# Cherry_MX.net
KiCad netlist of a schematic drawn in Altium Designer
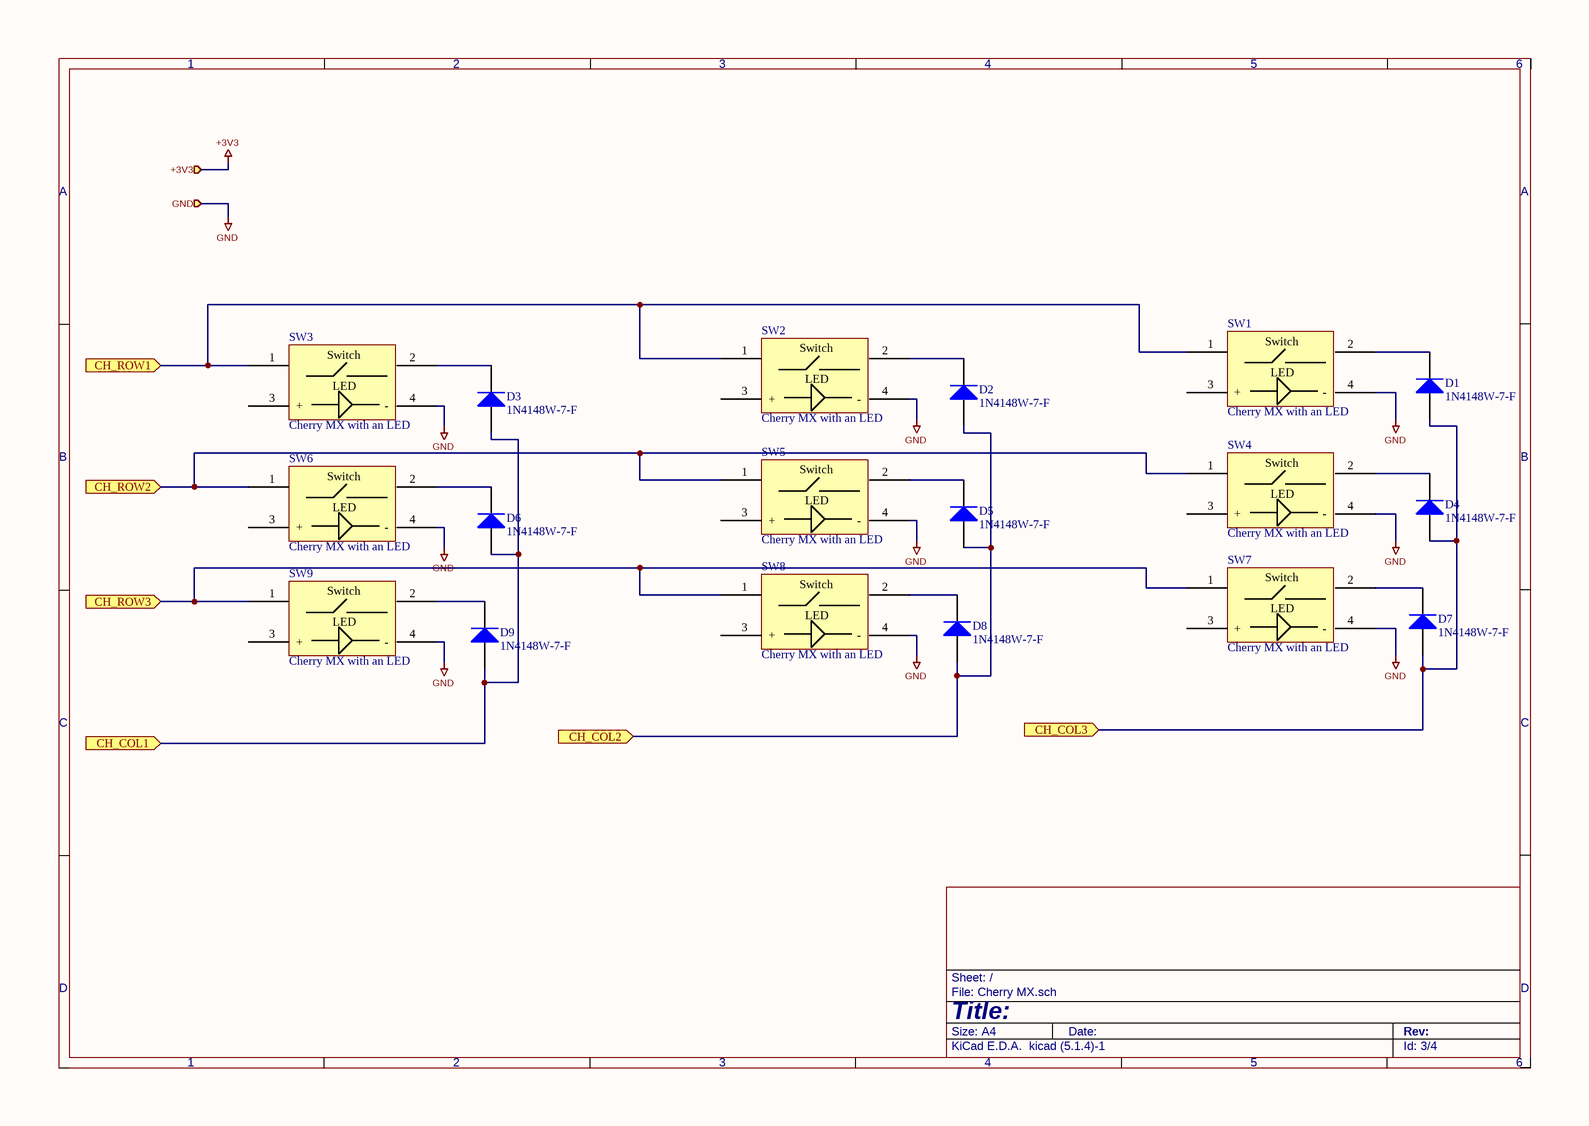
[diagram p0: Cherry MX.SchDoc]

(export (version "E")
  (design (tool "Eeschema 10.0.6"))
  (components
    (comp (ref "D1")
      (value "1N4148W-7-F")
      (footprint "DIOD-SOD123-2_V")
      (description "High Conductance Fast Diode")
      (fields (field (name "PUBLISHER") "Altium Limited"))
      (libsource (lib "Miscellaneous Devices") (part "Diode 1N4148"))
    )
    (comp (ref "D2")
      (value "1N4148W-7-F")
      (footprint "DIOD-SOD123-2_V")
      (description "High Conductance Fast Diode")
      (fields (field (name "PUBLISHER") "Altium Limited"))
      (libsource (lib "Miscellaneous Devices") (part "Diode 1N4148"))
    )
    (comp (ref "D3")
      (value "1N4148W-7-F")
      (footprint "DIOD-SOD123-2_V")
      (description "High Conductance Fast Diode")
      (fields (field (name "PUBLISHER") "Altium Limited"))
      (libsource (lib "Miscellaneous Devices") (part "Diode 1N4148"))
    )
    (comp (ref "D4")
      (value "1N4148W-7-F")
      (footprint "DIOD-SOD123-2_V")
      (description "High Conductance Fast Diode")
      (fields (field (name "PUBLISHER") "Altium Limited"))
      (libsource (lib "Miscellaneous Devices") (part "Diode 1N4148"))
    )
    (comp (ref "D5")
      (value "1N4148W-7-F")
      (footprint "DIOD-SOD123-2_V")
      (description "High Conductance Fast Diode")
      (fields (field (name "PUBLISHER") "Altium Limited"))
      (libsource (lib "Miscellaneous Devices") (part "Diode 1N4148"))
    )
    (comp (ref "D6")
      (value "1N4148W-7-F")
      (footprint "DIOD-SOD123-2_V")
      (description "High Conductance Fast Diode")
      (fields (field (name "PUBLISHER") "Altium Limited"))
      (libsource (lib "Miscellaneous Devices") (part "Diode 1N4148"))
    )
    (comp (ref "D7")
      (value "1N4148W-7-F")
      (footprint "DIOD-SOD123-2_V")
      (description "High Conductance Fast Diode")
      (fields (field (name "PUBLISHER") "Altium Limited"))
      (libsource (lib "Miscellaneous Devices") (part "Diode 1N4148"))
    )
    (comp (ref "D8")
      (value "1N4148W-7-F")
      (footprint "DIOD-SOD123-2_V")
      (description "High Conductance Fast Diode")
      (fields (field (name "PUBLISHER") "Altium Limited"))
      (libsource (lib "Miscellaneous Devices") (part "Diode 1N4148"))
    )
    (comp (ref "D9")
      (value "1N4148W-7-F")
      (footprint "DIOD-SOD123-2_V")
      (description "High Conductance Fast Diode")
      (fields (field (name "PUBLISHER") "Altium Limited"))
      (libsource (lib "Miscellaneous Devices") (part "Diode 1N4148"))
    )
    (comp (ref "SW1")
      (value "Cherry MX with an LED")
      (footprint "MX_Cherry_LED")
      (libsource (lib "PlumPot_Library") (part "MX_Cherry_LED"))
    )
    (comp (ref "SW2")
      (value "Cherry MX with an LED")
      (footprint "MX_Cherry_LED")
      (libsource (lib "PlumPot_Library") (part "MX_Cherry_LED"))
    )
    (comp (ref "SW3")
      (value "Cherry MX with an LED")
      (footprint "MX_Cherry_LED")
      (libsource (lib "PlumPot_Library") (part "MX_Cherry_LED"))
    )
    (comp (ref "SW4")
      (value "Cherry MX with an LED")
      (footprint "MX_Cherry_LED")
      (libsource (lib "PlumPot_Library") (part "MX_Cherry_LED"))
    )
    (comp (ref "SW5")
      (value "Cherry MX with an LED")
      (footprint "MX_Cherry_LED")
      (libsource (lib "PlumPot_Library") (part "MX_Cherry_LED"))
    )
    (comp (ref "SW6")
      (value "Cherry MX with an LED")
      (footprint "MX_Cherry_LED")
      (libsource (lib "PlumPot_Library") (part "MX_Cherry_LED"))
    )
    (comp (ref "SW7")
      (value "Cherry MX with an LED")
      (footprint "MX_Cherry_LED")
      (libsource (lib "PlumPot_Library") (part "MX_Cherry_LED"))
    )
    (comp (ref "SW8")
      (value "Cherry MX with an LED")
      (footprint "MX_Cherry_LED")
      (libsource (lib "PlumPot_Library") (part "MX_Cherry_LED"))
    )
    (comp (ref "SW9")
      (value "Cherry MX with an LED")
      (footprint "MX_Cherry_LED")
      (libsource (lib "PlumPot_Library") (part "MX_Cherry_LED"))
    )
  )
  (nets
    (net (code "2") (name "/CH_COL1") (class "Default")
      (node (ref "D3") (pin "1") (pinfunction "A_1") (pintype "passive"))
      (node (ref "D6") (pin "1") (pinfunction "A_1") (pintype "passive"))
      (node (ref "D9") (pin "1") (pinfunction "A_1") (pintype "passive"))
    )
    (net (code "3") (name "/CH_COL2") (class "Default")
      (node (ref "D2") (pin "1") (pinfunction "A_1") (pintype "passive"))
      (node (ref "D5") (pin "1") (pinfunction "A_1") (pintype "passive"))
      (node (ref "D8") (pin "1") (pinfunction "A_1") (pintype "passive"))
    )
    (net (code "4") (name "/CH_COL3") (class "Default")
      (node (ref "D1") (pin "1") (pinfunction "A_1") (pintype "passive"))
      (node (ref "D4") (pin "1") (pinfunction "A_1") (pintype "passive"))
      (node (ref "D7") (pin "1") (pinfunction "A_1") (pintype "passive"))
    )
    (net (code "5") (name "/CH_ROW1") (class "Default")
      (node (ref "SW1") (pin "1") (pintype "passive"))
      (node (ref "SW2") (pin "1") (pintype "passive"))
      (node (ref "SW3") (pin "1") (pintype "passive"))
    )
    (net (code "6") (name "/CH_ROW2") (class "Default")
      (node (ref "SW4") (pin "1") (pintype "passive"))
      (node (ref "SW5") (pin "1") (pintype "passive"))
      (node (ref "SW6") (pin "1") (pintype "passive"))
    )
    (net (code "7") (name "/CH_ROW3") (class "Default")
      (node (ref "SW7") (pin "1") (pintype "passive"))
      (node (ref "SW8") (pin "1") (pintype "passive"))
      (node (ref "SW9") (pin "1") (pintype "passive"))
    )
    (net (code "8") (name "GND") (class "Default")
      (node (ref "SW1") (pin "4") (pinfunction "-_4") (pintype "passive"))
      (node (ref "SW2") (pin "4") (pinfunction "-_4") (pintype "passive"))
      (node (ref "SW3") (pin "4") (pinfunction "-_4") (pintype "passive"))
      (node (ref "SW4") (pin "4") (pinfunction "-_4") (pintype "passive"))
      (node (ref "SW5") (pin "4") (pinfunction "-_4") (pintype "passive"))
      (node (ref "SW6") (pin "4") (pinfunction "-_4") (pintype "passive"))
      (node (ref "SW7") (pin "4") (pinfunction "-_4") (pintype "passive"))
      (node (ref "SW8") (pin "4") (pinfunction "-_4") (pintype "passive"))
      (node (ref "SW9") (pin "4") (pinfunction "-_4") (pintype "passive"))
    )
    (net (code "9") (name "Net-(D1-K)") (class "Default")
      (node (ref "D1") (pin "2") (pinfunction "K_2") (pintype "passive"))
      (node (ref "SW1") (pin "2") (pintype "passive"))
    )
    (net (code "10") (name "Net-(D2-K)") (class "Default")
      (node (ref "D2") (pin "2") (pinfunction "K_2") (pintype "passive"))
      (node (ref "SW2") (pin "2") (pintype "passive"))
    )
    (net (code "11") (name "Net-(D3-K)") (class "Default")
      (node (ref "D3") (pin "2") (pinfunction "K_2") (pintype "passive"))
      (node (ref "SW3") (pin "2") (pintype "passive"))
    )
    (net (code "12") (name "Net-(D4-K)") (class "Default")
      (node (ref "D4") (pin "2") (pinfunction "K_2") (pintype "passive"))
      (node (ref "SW4") (pin "2") (pintype "passive"))
    )
    (net (code "13") (name "Net-(D5-K)") (class "Default")
      (node (ref "D5") (pin "2") (pinfunction "K_2") (pintype "passive"))
      (node (ref "SW5") (pin "2") (pintype "passive"))
    )
    (net (code "14") (name "Net-(D6-K)") (class "Default")
      (node (ref "D6") (pin "2") (pinfunction "K_2") (pintype "passive"))
      (node (ref "SW6") (pin "2") (pintype "passive"))
    )
    (net (code "15") (name "Net-(D7-K)") (class "Default")
      (node (ref "D7") (pin "2") (pinfunction "K_2") (pintype "passive"))
      (node (ref "SW7") (pin "2") (pintype "passive"))
    )
    (net (code "16") (name "Net-(D8-K)") (class "Default")
      (node (ref "D8") (pin "2") (pinfunction "K_2") (pintype "passive"))
      (node (ref "SW8") (pin "2") (pintype "passive"))
    )
    (net (code "17") (name "Net-(D9-K)") (class "Default")
      (node (ref "D9") (pin "2") (pinfunction "K_2") (pintype "passive"))
      (node (ref "SW9") (pin "2") (pintype "passive"))
    )
    (net (code "18") (name "unconnected-(SW1-+-Pad3)") (class "Default")
      (node (ref "SW1") (pin "3") (pinfunction "+_3") (pintype "passive"))
    )
    (net (code "19") (name "unconnected-(SW2-+-Pad3)") (class "Default")
      (node (ref "SW2") (pin "3") (pinfunction "+_3") (pintype "passive"))
    )
    (net (code "20") (name "unconnected-(SW3-+-Pad3)") (class "Default")
      (node (ref "SW3") (pin "3") (pinfunction "+_3") (pintype "passive"))
    )
    (net (code "21") (name "unconnected-(SW4-+-Pad3)") (class "Default")
      (node (ref "SW4") (pin "3") (pinfunction "+_3") (pintype "passive"))
    )
    (net (code "22") (name "unconnected-(SW5-+-Pad3)") (class "Default")
      (node (ref "SW5") (pin "3") (pinfunction "+_3") (pintype "passive"))
    )
    (net (code "23") (name "unconnected-(SW6-+-Pad3)") (class "Default")
      (node (ref "SW6") (pin "3") (pinfunction "+_3") (pintype "passive"))
    )
    (net (code "24") (name "unconnected-(SW7-+-Pad3)") (class "Default")
      (node (ref "SW7") (pin "3") (pinfunction "+_3") (pintype "passive"))
    )
    (net (code "25") (name "unconnected-(SW8-+-Pad3)") (class "Default")
      (node (ref "SW8") (pin "3") (pinfunction "+_3") (pintype "passive"))
    )
    (net (code "26") (name "unconnected-(SW9-+-Pad3)") (class "Default")
      (node (ref "SW9") (pin "3") (pinfunction "+_3") (pintype "passive"))
    )
  )
)
